# M651X.net
KiCad netlist of a schematic drawn in EAGLE
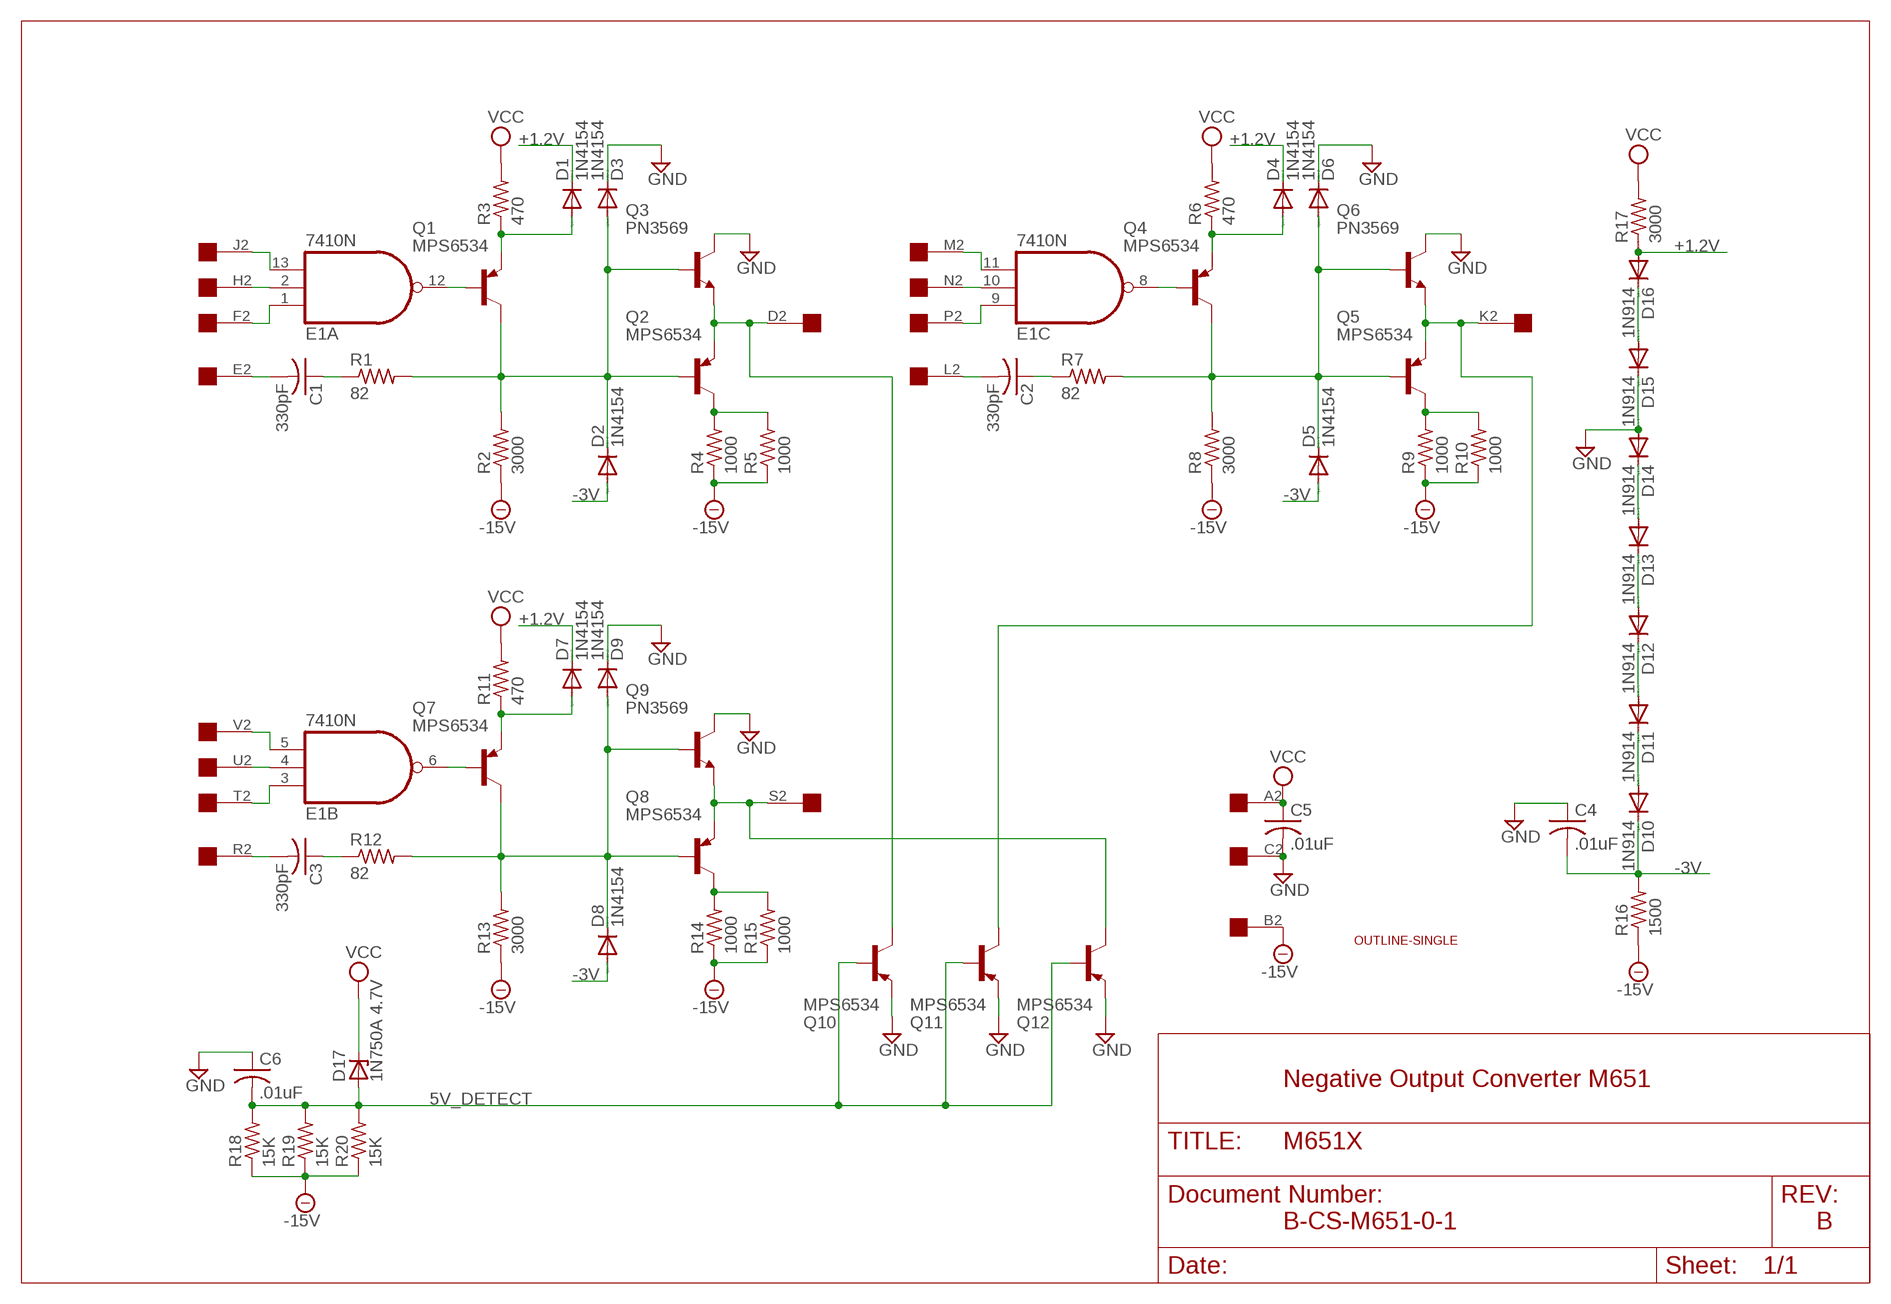
[diagram p0: schematic, sheet 1]

(export (version "E")
  (design (tool "Eeschema 10.0.6"))
  (components
    (comp (ref "C1")
      (value "330pF")
      (footprint "eagle-import:C050-025X075")
      (libsource (lib "eagle-import") (part "C-US050-025X075"))
    )
    (comp (ref "C2")
      (value "330pF")
      (footprint "eagle-import:C050-025X075")
      (libsource (lib "eagle-import") (part "C-US050-025X075"))
    )
    (comp (ref "C3")
      (value "330pF")
      (footprint "eagle-import:C050-025X075")
      (libsource (lib "eagle-import") (part "C-US050-025X075"))
    )
    (comp (ref "C4")
      (value ".01uF")
      (footprint "eagle-import:C050-025X075")
      (libsource (lib "eagle-import") (part "C-US050-025X075"))
    )
    (comp (ref "C5")
      (value ".01uF")
      (footprint "eagle-import:C050-025X075")
      (libsource (lib "eagle-import") (part "C-US050-025X075"))
    )
    (comp (ref "C6")
      (value ".01uF")
      (footprint "eagle-import:C050-025X075")
      (libsource (lib "eagle-import") (part "C-US050-025X075"))
    )
    (comp (ref "D1")
      (value "1N4154")
      (footprint "eagle-import:DO35-10")
      (libsource (lib "eagle-import") (part "1N4148DO35-10"))
    )
    (comp (ref "D2")
      (value "1N4154")
      (footprint "eagle-import:DO35-10")
      (libsource (lib "eagle-import") (part "1N4148DO35-10"))
    )
    (comp (ref "D3")
      (value "1N4154")
      (footprint "eagle-import:DO35-10")
      (libsource (lib "eagle-import") (part "1N4148DO35-10"))
    )
    (comp (ref "D4")
      (value "1N4154")
      (footprint "eagle-import:DO35-10")
      (libsource (lib "eagle-import") (part "1N4148DO35-10"))
    )
    (comp (ref "D5")
      (value "1N4154")
      (footprint "eagle-import:DO35-10")
      (libsource (lib "eagle-import") (part "1N4148DO35-10"))
    )
    (comp (ref "D6")
      (value "1N4154")
      (footprint "eagle-import:DO35-10")
      (libsource (lib "eagle-import") (part "1N4148DO35-10"))
    )
    (comp (ref "D7")
      (value "1N4154")
      (footprint "eagle-import:DO35-10")
      (libsource (lib "eagle-import") (part "1N4148DO35-10"))
    )
    (comp (ref "D8")
      (value "1N4154")
      (footprint "eagle-import:DO35-10")
      (libsource (lib "eagle-import") (part "1N4148DO35-10"))
    )
    (comp (ref "D9")
      (value "1N4154")
      (footprint "eagle-import:DO35-10")
      (libsource (lib "eagle-import") (part "1N4148DO35-10"))
    )
    (comp (ref "D10")
      (value "1N914")
      (footprint "eagle-import:DO35-10")
      (libsource (lib "eagle-import") (part "1N4148DO35-10"))
    )
    (comp (ref "D11")
      (value "1N914")
      (footprint "eagle-import:DO35-10")
      (libsource (lib "eagle-import") (part "1N4148DO35-10"))
    )
    (comp (ref "D12")
      (value "1N914")
      (footprint "eagle-import:DO35-10")
      (libsource (lib "eagle-import") (part "1N4148DO35-10"))
    )
    (comp (ref "D13")
      (value "1N914")
      (footprint "eagle-import:DO35-10")
      (libsource (lib "eagle-import") (part "1N4148DO35-10"))
    )
    (comp (ref "D14")
      (value "1N914")
      (footprint "eagle-import:DO35-10")
      (libsource (lib "eagle-import") (part "1N4148DO35-10"))
    )
    (comp (ref "D15")
      (value "1N914")
      (footprint "eagle-import:DO35-10")
      (libsource (lib "eagle-import") (part "1N4148DO35-10"))
    )
    (comp (ref "D16")
      (value "1N914")
      (footprint "eagle-import:DO35-10")
      (libsource (lib "eagle-import") (part "1N4148DO35-10"))
    )
    (comp (ref "D17")
      (value "1N750A 4.7V")
      (footprint "eagle-import:DO35Z10")
      (libsource (lib "eagle-import") (part "ZENER-DIODEDO35Z10"))
    )
    (comp (ref "E1")
      (value "7410N")
      (footprint "eagle-import:DIL14")
      (libsource (lib "eagle-import") (part "7410N"))
    )
    (comp (ref "Q1")
      (value "MPS6534")
      (footprint "eagle-import:TO39")
      (libsource (lib "eagle-import") (part "2N5415"))
    )
    (comp (ref "Q2")
      (value "MPS6534")
      (footprint "eagle-import:TO39")
      (libsource (lib "eagle-import") (part "2N5415"))
    )
    (comp (ref "Q3")
      (value "PN3569")
      (footprint "eagle-import:TO5")
      (libsource (lib "eagle-import") (part "2N2219"))
    )
    (comp (ref "Q4")
      (value "MPS6534")
      (footprint "eagle-import:TO39")
      (libsource (lib "eagle-import") (part "2N5415"))
    )
    (comp (ref "Q5")
      (value "MPS6534")
      (footprint "eagle-import:TO39")
      (libsource (lib "eagle-import") (part "2N5415"))
    )
    (comp (ref "Q6")
      (value "PN3569")
      (footprint "eagle-import:TO5")
      (libsource (lib "eagle-import") (part "2N2219"))
    )
    (comp (ref "Q7")
      (value "MPS6534")
      (footprint "eagle-import:TO39")
      (libsource (lib "eagle-import") (part "2N5415"))
    )
    (comp (ref "Q8")
      (value "MPS6534")
      (footprint "eagle-import:TO39")
      (libsource (lib "eagle-import") (part "2N5415"))
    )
    (comp (ref "Q9")
      (value "PN3569")
      (footprint "eagle-import:TO5")
      (libsource (lib "eagle-import") (part "2N2219"))
    )
    (comp (ref "Q10")
      (value "MPS6534")
      (footprint "eagle-import:TO39")
      (libsource (lib "eagle-import") (part "2N5415"))
    )
    (comp (ref "Q11")
      (value "MPS6534")
      (footprint "eagle-import:TO39")
      (libsource (lib "eagle-import") (part "2N5415"))
    )
    (comp (ref "Q12")
      (value "MPS6534")
      (footprint "eagle-import:TO39")
      (libsource (lib "eagle-import") (part "2N5415"))
    )
    (comp (ref "R1")
      (value "82")
      (footprint "eagle-import:0207_10")
      (libsource (lib "eagle-import") (part "R-US_0207/10"))
    )
    (comp (ref "R2")
      (value "3000")
      (footprint "eagle-import:0207_10")
      (libsource (lib "eagle-import") (part "R-US_0207/10"))
    )
    (comp (ref "R3")
      (value "470")
      (footprint "eagle-import:0207_10")
      (libsource (lib "eagle-import") (part "R-US_0207/10"))
    )
    (comp (ref "R4")
      (value "1000")
      (footprint "eagle-import:0207_10")
      (libsource (lib "eagle-import") (part "R-US_0207/10"))
    )
    (comp (ref "R5")
      (value "1000")
      (footprint "eagle-import:0207_10")
      (libsource (lib "eagle-import") (part "R-US_0207/10"))
    )
    (comp (ref "R6")
      (value "470")
      (footprint "eagle-import:0207_10")
      (libsource (lib "eagle-import") (part "R-US_0207/10"))
    )
    (comp (ref "R7")
      (value "82")
      (footprint "eagle-import:0207_10")
      (libsource (lib "eagle-import") (part "R-US_0207/10"))
    )
    (comp (ref "R8")
      (value "3000")
      (footprint "eagle-import:0207_10")
      (libsource (lib "eagle-import") (part "R-US_0207/10"))
    )
    (comp (ref "R9")
      (value "1000")
      (footprint "eagle-import:0207_10")
      (libsource (lib "eagle-import") (part "R-US_0207/10"))
    )
    (comp (ref "R10")
      (value "1000")
      (footprint "eagle-import:0207_10")
      (libsource (lib "eagle-import") (part "R-US_0207/10"))
    )
    (comp (ref "R11")
      (value "470")
      (footprint "eagle-import:0207_10")
      (libsource (lib "eagle-import") (part "R-US_0207/10"))
    )
    (comp (ref "R12")
      (value "82")
      (footprint "eagle-import:0207_10")
      (libsource (lib "eagle-import") (part "R-US_0207/10"))
    )
    (comp (ref "R13")
      (value "3000")
      (footprint "eagle-import:0207_10")
      (libsource (lib "eagle-import") (part "R-US_0207/10"))
    )
    (comp (ref "R14")
      (value "1000")
      (footprint "eagle-import:0207_10")
      (libsource (lib "eagle-import") (part "R-US_0207/10"))
    )
    (comp (ref "R15")
      (value "1000")
      (footprint "eagle-import:0207_10")
      (libsource (lib "eagle-import") (part "R-US_0207/10"))
    )
    (comp (ref "R16")
      (value "1500")
      (footprint "eagle-import:0207_10")
      (libsource (lib "eagle-import") (part "R-US_0207/10"))
    )
    (comp (ref "R17")
      (value "3000")
      (footprint "eagle-import:0207_10")
      (libsource (lib "eagle-import") (part "R-US_0207/10"))
    )
    (comp (ref "R18")
      (value "15K")
      (footprint "eagle-import:0207_10")
      (libsource (lib "eagle-import") (part "R-US_0207/10"))
    )
    (comp (ref "R19")
      (value "15K")
      (footprint "eagle-import:0207_10")
      (libsource (lib "eagle-import") (part "R-US_0207/10"))
    )
    (comp (ref "R20")
      (value "15K")
      (footprint "eagle-import:0207_10")
      (libsource (lib "eagle-import") (part "R-US_0207/10"))
    )
    (comp (ref "U$1")
      (value "OUTLINE-SINGLE")
      (footprint "eagle-import:SINGLE")
      (libsource (lib "eagle-import") (part "OUTLINE-SINGLE"))
    )
    (comp (ref "U$3")
      (value "EDGE-1")
      (footprint "eagle-import:EDGE-CON1")
      (libsource (lib "eagle-import") (part "EDGE-1"))
    )
  )
  (nets
    (net (code "1") (name "-15V") (class "Default")
      (node (ref "R10") (pin "1") (pinfunction "1_1") (pintype "passive"))
      (node (ref "R13") (pin "1") (pinfunction "1_1") (pintype "passive"))
      (node (ref "R14") (pin "1") (pinfunction "1_1") (pintype "passive"))
      (node (ref "R15") (pin "1") (pinfunction "1_1") (pintype "passive"))
      (node (ref "R16") (pin "1") (pinfunction "1_1") (pintype "passive"))
      (node (ref "R18") (pin "1") (pinfunction "1_1") (pintype "passive"))
      (node (ref "R19") (pin "1") (pinfunction "1_1") (pintype "passive"))
      (node (ref "R2") (pin "1") (pinfunction "1_1") (pintype "passive"))
      (node (ref "R20") (pin "1") (pinfunction "1_1") (pintype "passive"))
      (node (ref "R4") (pin "1") (pinfunction "1_1") (pintype "passive"))
      (node (ref "R5") (pin "1") (pinfunction "1_1") (pintype "passive"))
      (node (ref "R8") (pin "1") (pinfunction "1_1") (pintype "passive"))
      (node (ref "R9") (pin "1") (pinfunction "1_1") (pintype "passive"))
      (node (ref "U$3") (pin "B2") (pinfunction "1_B2") (pintype "bidirectional"))
    )
    (net (code "2") (name "/+1.2V") (class "Default")
      (node (ref "D1") (pin "C") (pinfunction "C_C") (pintype "passive"))
      (node (ref "D16") (pin "A") (pinfunction "A_A") (pintype "passive"))
      (node (ref "D4") (pin "C") (pinfunction "C_C") (pintype "passive"))
      (node (ref "D7") (pin "C") (pinfunction "C_C") (pintype "passive"))
      (node (ref "R17") (pin "1") (pinfunction "1_1") (pintype "passive"))
    )
    (net (code "3") (name "/-3V") (class "Default")
      (node (ref "C4") (pin "2") (pinfunction "2_2") (pintype "passive"))
      (node (ref "D10") (pin "C") (pinfunction "C_C") (pintype "passive"))
      (node (ref "D2") (pin "A") (pinfunction "A_A") (pintype "passive"))
      (node (ref "D5") (pin "A") (pinfunction "A_A") (pintype "passive"))
      (node (ref "D8") (pin "A") (pinfunction "A_A") (pintype "passive"))
      (node (ref "R16") (pin "2") (pinfunction "2_2") (pintype "passive"))
    )
    (net (code "4") (name "/5V_DETECT") (class "Default")
      (node (ref "C6") (pin "2") (pinfunction "2_2") (pintype "passive"))
      (node (ref "D17") (pin "A") (pinfunction "A_A") (pintype "passive"))
      (node (ref "Q10") (pin "2") (pinfunction "B_2") (pintype "passive"))
      (node (ref "Q11") (pin "2") (pinfunction "B_2") (pintype "passive"))
      (node (ref "Q12") (pin "2") (pinfunction "B_2") (pintype "passive"))
      (node (ref "R18") (pin "2") (pinfunction "2_2") (pintype "passive"))
      (node (ref "R19") (pin "2") (pinfunction "2_2") (pintype "passive"))
      (node (ref "R20") (pin "2") (pinfunction "2_2") (pintype "passive"))
    )
    (net (code "5") (name "GND") (class "Default")
      (node (ref "C4") (pin "1") (pinfunction "1_1") (pintype "passive"))
      (node (ref "C5") (pin "2") (pinfunction "2_2") (pintype "passive"))
      (node (ref "C6") (pin "1") (pinfunction "1_1") (pintype "passive"))
      (node (ref "D14") (pin "A") (pinfunction "A_A") (pintype "passive"))
      (node (ref "D15") (pin "C") (pinfunction "C_C") (pintype "passive"))
      (node (ref "D3") (pin "C") (pinfunction "C_C") (pintype "passive"))
      (node (ref "D6") (pin "C") (pinfunction "C_C") (pintype "passive"))
      (node (ref "D9") (pin "C") (pinfunction "C_C") (pintype "passive"))
      (node (ref "Q10") (pin "1") (pinfunction "E_1") (pintype "passive"))
      (node (ref "Q11") (pin "1") (pinfunction "E_1") (pintype "passive"))
      (node (ref "Q12") (pin "1") (pinfunction "E_1") (pintype "passive"))
      (node (ref "Q3") (pin "3") (pinfunction "C_3") (pintype "passive"))
      (node (ref "Q6") (pin "3") (pinfunction "C_3") (pintype "passive"))
      (node (ref "Q9") (pin "3") (pinfunction "C_3") (pintype "passive"))
      (node (ref "U$3") (pin "C2") (pinfunction "1_C2") (pintype "bidirectional"))
    )
    (net (code "6") (name "Net-(C1-Pad1)") (class "Default")
      (node (ref "C1") (pin "1") (pinfunction "1_1") (pintype "passive"))
      (node (ref "R1") (pin "1") (pinfunction "1_1") (pintype "passive"))
    )
    (net (code "7") (name "Net-(C2-Pad1)") (class "Default")
      (node (ref "C2") (pin "1") (pinfunction "1_1") (pintype "passive"))
      (node (ref "R7") (pin "1") (pinfunction "1_1") (pintype "passive"))
    )
    (net (code "8") (name "Net-(C3-Pad1)") (class "Default")
      (node (ref "C3") (pin "1") (pinfunction "1_1") (pintype "passive"))
      (node (ref "R12") (pin "1") (pinfunction "1_1") (pintype "passive"))
    )
    (net (code "9") (name "Net-(D10-PadA)") (class "Default")
      (node (ref "D10") (pin "A") (pinfunction "A_A") (pintype "passive"))
      (node (ref "D11") (pin "C") (pinfunction "C_C") (pintype "passive"))
    )
    (net (code "10") (name "Net-(D11-PadA)") (class "Default")
      (node (ref "D11") (pin "A") (pinfunction "A_A") (pintype "passive"))
      (node (ref "D12") (pin "C") (pinfunction "C_C") (pintype "passive"))
    )
    (net (code "11") (name "Net-(D12-PadA)") (class "Default")
      (node (ref "D12") (pin "A") (pinfunction "A_A") (pintype "passive"))
      (node (ref "D13") (pin "C") (pinfunction "C_C") (pintype "passive"))
    )
    (net (code "12") (name "Net-(D13-PadA)") (class "Default")
      (node (ref "D13") (pin "A") (pinfunction "A_A") (pintype "passive"))
      (node (ref "D14") (pin "C") (pinfunction "C_C") (pintype "passive"))
    )
    (net (code "13") (name "Net-(D15-PadA)") (class "Default")
      (node (ref "D15") (pin "A") (pinfunction "A_A") (pintype "passive"))
      (node (ref "D16") (pin "C") (pinfunction "C_C") (pintype "passive"))
    )
    (net (code "14") (name "Net-(E1A-I0)") (class "Default")
      (node (ref "E1") (pin "1") (pinfunction "I0_1") (pintype "input"))
      (node (ref "U$3") (pin "F2") (pinfunction "1_F2") (pintype "bidirectional"))
    )
    (net (code "15") (name "Net-(E1A-I1)") (class "Default")
      (node (ref "E1") (pin "2") (pinfunction "I1_2") (pintype "input"))
      (node (ref "U$3") (pin "H2") (pinfunction "1_H2") (pintype "bidirectional"))
    )
    (net (code "16") (name "Net-(E1A-I2)") (class "Default")
      (node (ref "E1") (pin "13") (pinfunction "I2_13") (pintype "input"))
      (node (ref "U$3") (pin "J2") (pinfunction "1_J2") (pintype "bidirectional"))
    )
    (net (code "17") (name "Net-(E1A-O)") (class "Default")
      (node (ref "E1") (pin "12") (pinfunction "O_12") (pintype "output"))
      (node (ref "Q1") (pin "2") (pinfunction "B_2") (pintype "passive"))
    )
    (net (code "18") (name "Net-(E1B-I0)") (class "Default")
      (node (ref "E1") (pin "3") (pinfunction "I0_3") (pintype "input"))
      (node (ref "U$3") (pin "T2") (pinfunction "1_T2") (pintype "bidirectional"))
    )
    (net (code "19") (name "Net-(E1B-I1)") (class "Default")
      (node (ref "E1") (pin "4") (pinfunction "I1_4") (pintype "input"))
      (node (ref "U$3") (pin "U2") (pinfunction "1_U2") (pintype "bidirectional"))
    )
    (net (code "20") (name "Net-(E1B-I2)") (class "Default")
      (node (ref "E1") (pin "5") (pinfunction "I2_5") (pintype "input"))
      (node (ref "U$3") (pin "V2") (pinfunction "1_V2") (pintype "bidirectional"))
    )
    (net (code "21") (name "Net-(E1B-O)") (class "Default")
      (node (ref "E1") (pin "6") (pinfunction "O_6") (pintype "output"))
      (node (ref "Q7") (pin "2") (pinfunction "B_2") (pintype "passive"))
    )
    (net (code "22") (name "Net-(E1C-I0)") (class "Default")
      (node (ref "E1") (pin "9") (pinfunction "I0_9") (pintype "input"))
      (node (ref "U$3") (pin "P2") (pinfunction "1_P2") (pintype "bidirectional"))
    )
    (net (code "23") (name "Net-(E1C-I1)") (class "Default")
      (node (ref "E1") (pin "10") (pinfunction "I1_10") (pintype "input"))
      (node (ref "U$3") (pin "N2") (pinfunction "1_N2") (pintype "bidirectional"))
    )
    (net (code "24") (name "Net-(E1C-I2)") (class "Default")
      (node (ref "E1") (pin "11") (pinfunction "I2_11") (pintype "input"))
      (node (ref "U$3") (pin "M2") (pinfunction "1_M2") (pintype "bidirectional"))
    )
    (net (code "25") (name "Net-(E1C-O)") (class "Default")
      (node (ref "E1") (pin "8") (pinfunction "O_8") (pintype "output"))
      (node (ref "Q4") (pin "2") (pinfunction "B_2") (pintype "passive"))
    )
    (net (code "26") (name "Net-(Q1-C)") (class "Default")
      (node (ref "D2") (pin "C") (pinfunction "C_C") (pintype "passive"))
      (node (ref "D3") (pin "A") (pinfunction "A_A") (pintype "passive"))
      (node (ref "Q1") (pin "3") (pinfunction "C_3") (pintype "passive"))
      (node (ref "Q2") (pin "2") (pinfunction "B_2") (pintype "passive"))
      (node (ref "Q3") (pin "2") (pinfunction "B_2") (pintype "passive"))
      (node (ref "R1") (pin "2") (pinfunction "2_2") (pintype "passive"))
      (node (ref "R2") (pin "2") (pinfunction "2_2") (pintype "passive"))
    )
    (net (code "27") (name "Net-(Q1-E)") (class "Default")
      (node (ref "D1") (pin "A") (pinfunction "A_A") (pintype "passive"))
      (node (ref "Q1") (pin "1") (pinfunction "E_1") (pintype "passive"))
      (node (ref "R3") (pin "1") (pinfunction "1_1") (pintype "passive"))
    )
    (net (code "28") (name "Net-(Q2-C)") (class "Default")
      (node (ref "Q2") (pin "3") (pinfunction "C_3") (pintype "passive"))
      (node (ref "R4") (pin "2") (pinfunction "2_2") (pintype "passive"))
      (node (ref "R5") (pin "2") (pinfunction "2_2") (pintype "passive"))
    )
    (net (code "29") (name "Net-(Q4-C)") (class "Default")
      (node (ref "D5") (pin "C") (pinfunction "C_C") (pintype "passive"))
      (node (ref "D6") (pin "A") (pinfunction "A_A") (pintype "passive"))
      (node (ref "Q4") (pin "3") (pinfunction "C_3") (pintype "passive"))
      (node (ref "Q5") (pin "2") (pinfunction "B_2") (pintype "passive"))
      (node (ref "Q6") (pin "2") (pinfunction "B_2") (pintype "passive"))
      (node (ref "R7") (pin "2") (pinfunction "2_2") (pintype "passive"))
      (node (ref "R8") (pin "2") (pinfunction "2_2") (pintype "passive"))
    )
    (net (code "30") (name "Net-(Q4-E)") (class "Default")
      (node (ref "D4") (pin "A") (pinfunction "A_A") (pintype "passive"))
      (node (ref "Q4") (pin "1") (pinfunction "E_1") (pintype "passive"))
      (node (ref "R6") (pin "1") (pinfunction "1_1") (pintype "passive"))
    )
    (net (code "31") (name "Net-(Q5-C)") (class "Default")
      (node (ref "Q5") (pin "3") (pinfunction "C_3") (pintype "passive"))
      (node (ref "R10") (pin "2") (pinfunction "2_2") (pintype "passive"))
      (node (ref "R9") (pin "2") (pinfunction "2_2") (pintype "passive"))
    )
    (net (code "32") (name "Net-(Q7-C)") (class "Default")
      (node (ref "D8") (pin "C") (pinfunction "C_C") (pintype "passive"))
      (node (ref "D9") (pin "A") (pinfunction "A_A") (pintype "passive"))
      (node (ref "Q7") (pin "3") (pinfunction "C_3") (pintype "passive"))
      (node (ref "Q8") (pin "2") (pinfunction "B_2") (pintype "passive"))
      (node (ref "Q9") (pin "2") (pinfunction "B_2") (pintype "passive"))
      (node (ref "R12") (pin "2") (pinfunction "2_2") (pintype "passive"))
      (node (ref "R13") (pin "2") (pinfunction "2_2") (pintype "passive"))
    )
    (net (code "33") (name "Net-(Q7-E)") (class "Default")
      (node (ref "D7") (pin "A") (pinfunction "A_A") (pintype "passive"))
      (node (ref "Q7") (pin "1") (pinfunction "E_1") (pintype "passive"))
      (node (ref "R11") (pin "1") (pinfunction "1_1") (pintype "passive"))
    )
    (net (code "34") (name "Net-(Q8-C)") (class "Default")
      (node (ref "Q8") (pin "3") (pinfunction "C_3") (pintype "passive"))
      (node (ref "R14") (pin "2") (pinfunction "2_2") (pintype "passive"))
      (node (ref "R15") (pin "2") (pinfunction "2_2") (pintype "passive"))
    )
    (net (code "35") (name "Net-(Q10-C)") (class "Default")
      (node (ref "Q10") (pin "3") (pinfunction "C_3") (pintype "passive"))
      (node (ref "Q2") (pin "1") (pinfunction "E_1") (pintype "passive"))
      (node (ref "Q3") (pin "1") (pinfunction "E_1") (pintype "passive"))
      (node (ref "U$3") (pin "D2") (pinfunction "1_D2") (pintype "bidirectional"))
    )
    (net (code "36") (name "Net-(Q11-C)") (class "Default")
      (node (ref "Q11") (pin "3") (pinfunction "C_3") (pintype "passive"))
      (node (ref "Q5") (pin "1") (pinfunction "E_1") (pintype "passive"))
      (node (ref "Q6") (pin "1") (pinfunction "E_1") (pintype "passive"))
      (node (ref "U$3") (pin "K2") (pinfunction "1_K2") (pintype "bidirectional"))
    )
    (net (code "37") (name "Net-(Q12-C)") (class "Default")
      (node (ref "Q12") (pin "3") (pinfunction "C_3") (pintype "passive"))
      (node (ref "Q8") (pin "1") (pinfunction "E_1") (pintype "passive"))
      (node (ref "Q9") (pin "1") (pinfunction "E_1") (pintype "passive"))
      (node (ref "U$3") (pin "S2") (pinfunction "1_S2") (pintype "bidirectional"))
    )
    (net (code "38") (name "Net-(U$3E-1)") (class "Default")
      (node (ref "C1") (pin "2") (pinfunction "2_2") (pintype "passive"))
      (node (ref "U$3") (pin "E2") (pinfunction "1_E2") (pintype "bidirectional"))
    )
    (net (code "39") (name "Net-(U$3J-1)") (class "Default")
      (node (ref "C2") (pin "2") (pinfunction "2_2") (pintype "passive"))
      (node (ref "U$3") (pin "L2") (pinfunction "1_L2") (pintype "bidirectional"))
    )
    (net (code "40") (name "Net-(U$3N-1)") (class "Default")
      (node (ref "C3") (pin "2") (pinfunction "2_2") (pintype "passive"))
      (node (ref "U$3") (pin "R2") (pinfunction "1_R2") (pintype "bidirectional"))
    )
    (net (code "41") (name "VCC") (class "Default")
      (node (ref "C5") (pin "1") (pinfunction "1_1") (pintype "passive"))
      (node (ref "D17") (pin "C") (pinfunction "C_C") (pintype "passive"))
      (node (ref "R11") (pin "2") (pinfunction "2_2") (pintype "passive"))
      (node (ref "R17") (pin "2") (pinfunction "2_2") (pintype "passive"))
      (node (ref "R3") (pin "2") (pinfunction "2_2") (pintype "passive"))
      (node (ref "R6") (pin "2") (pinfunction "2_2") (pintype "passive"))
      (node (ref "U$3") (pin "A2") (pinfunction "1_A2") (pintype "bidirectional"))
    )
  )
)
